# adder_subtractor.net
KiCad netlist of a schematic drawn in EAGLE
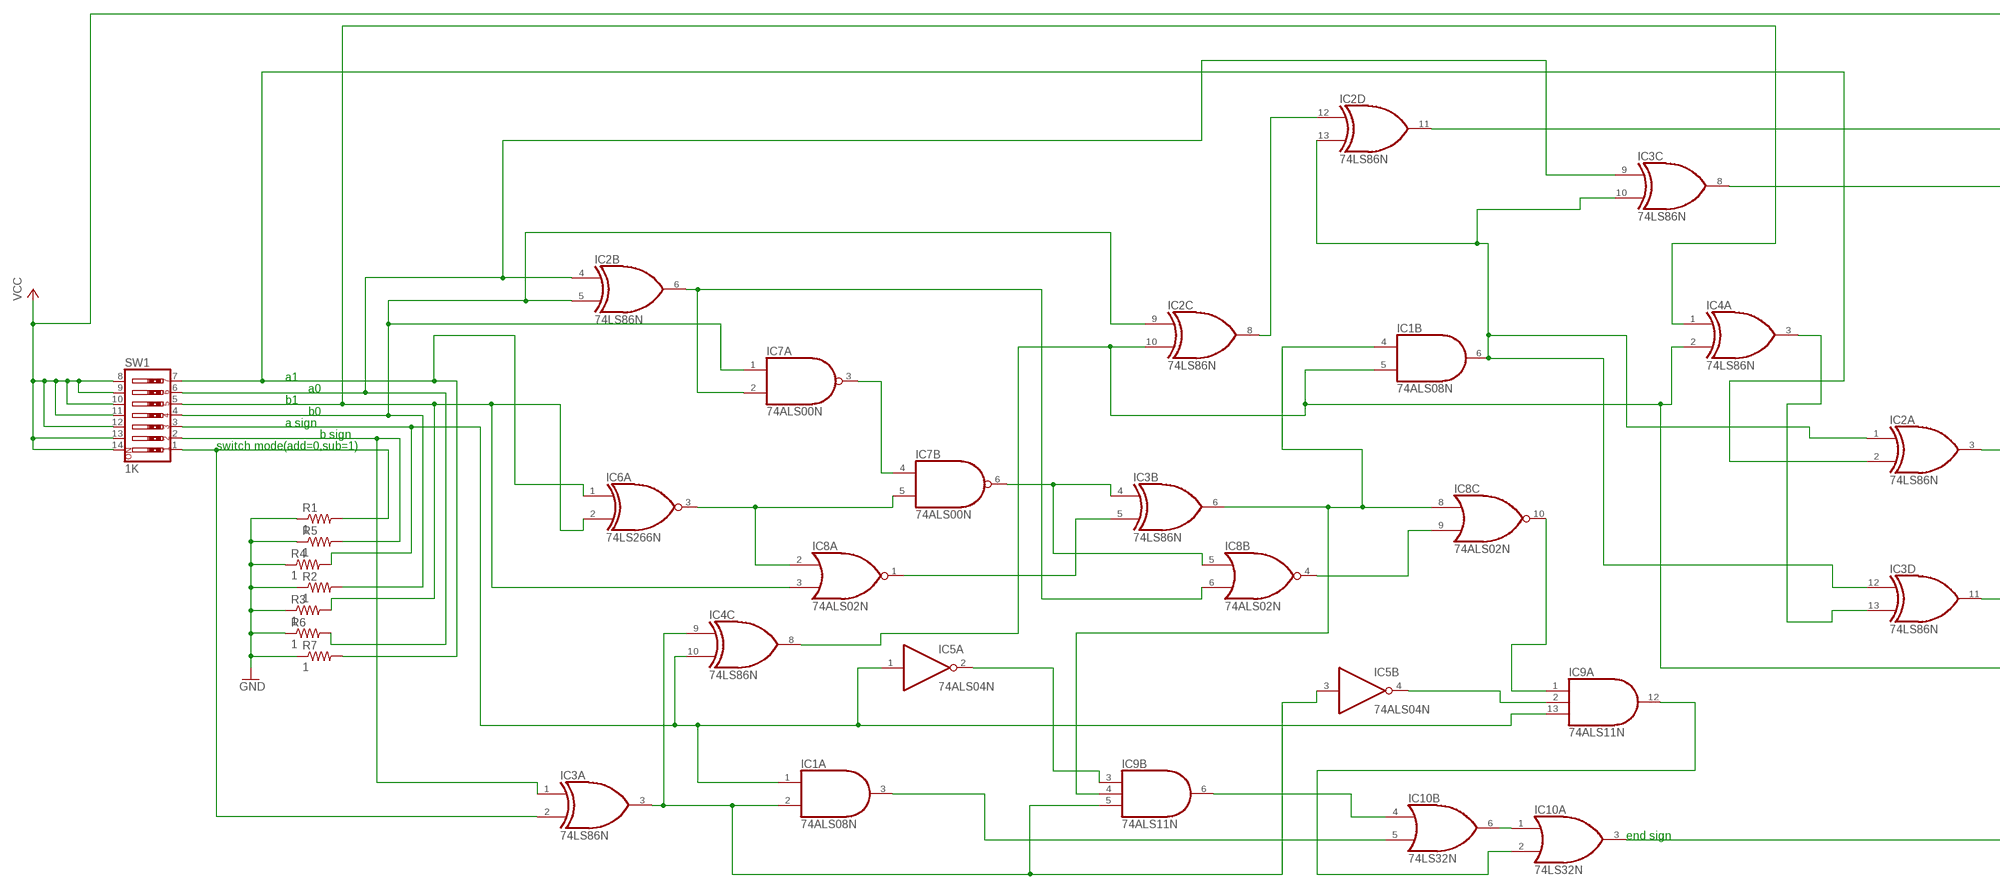
[diagram p0: schematic, sheet 1, part 1 of 2]
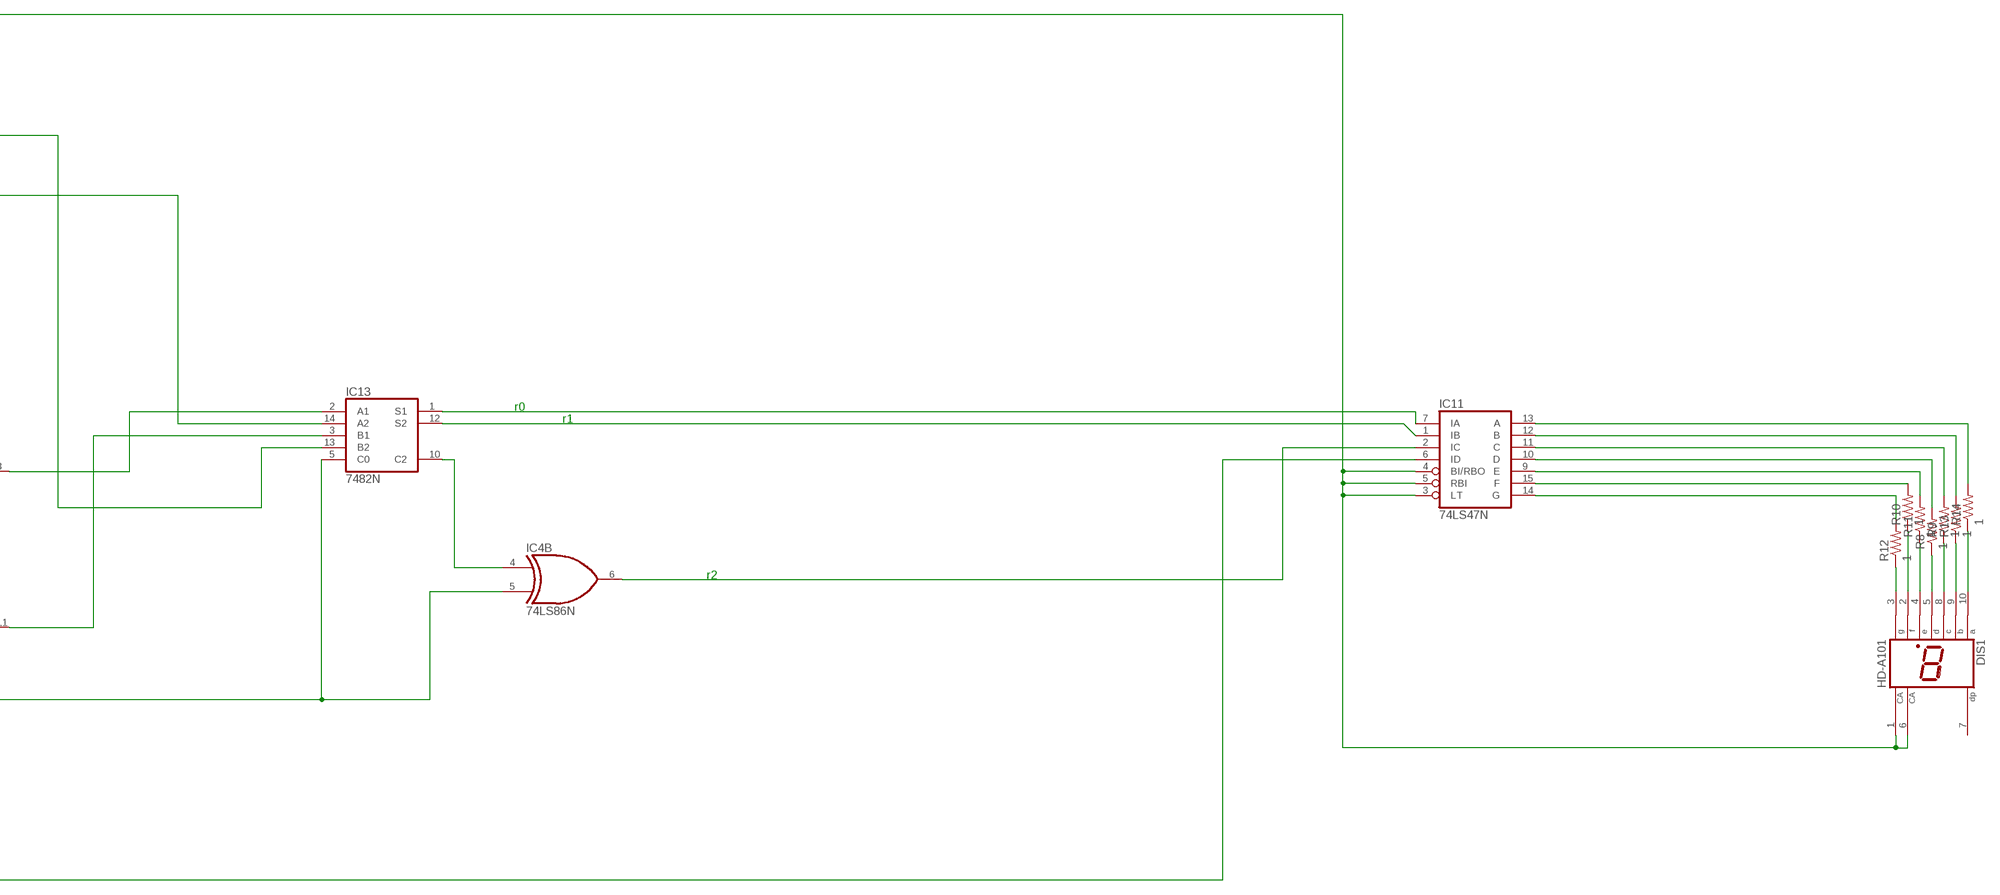
[diagram p1: schematic, sheet 1, part 2 of 2]

(export (version "E")
  (design (tool "Eeschema 10.0.6"))
  (components
    (comp (ref "DIS1")
      (value "HD-A101")
      (footprint "eagle-import:HDSP-A")
      (libsource (lib "eagle-import") (part "HD-A101"))
    )
    (comp (ref "IC1")
      (value "74ALS08N")
      (footprint "eagle-import:DIL14")
      (libsource (lib "eagle-import") (part "7408NALS"))
    )
    (comp (ref "IC2")
      (value "74LS86N")
      (footprint "eagle-import:DIL14")
      (libsource (lib "eagle-import") (part "7486NLS"))
    )
    (comp (ref "IC3")
      (value "74LS86N")
      (footprint "eagle-import:DIL14")
      (libsource (lib "eagle-import") (part "7486NLS"))
    )
    (comp (ref "IC4")
      (value "74LS86N")
      (footprint "eagle-import:DIL14")
      (libsource (lib "eagle-import") (part "7486NLS"))
    )
    (comp (ref "IC5")
      (value "74ALS04N")
      (footprint "eagle-import:DIL14")
      (libsource (lib "eagle-import") (part "7404NALS"))
    )
    (comp (ref "IC6")
      (value "74LS266N")
      (footprint "eagle-import:DIL14")
      (libsource (lib "eagle-import") (part "74266NLS"))
    )
    (comp (ref "IC7")
      (value "74ALS00N")
      (footprint "eagle-import:DIL14")
      (libsource (lib "eagle-import") (part "7400NALS"))
    )
    (comp (ref "IC8")
      (value "74ALS02N")
      (footprint "eagle-import:DIL14")
      (libsource (lib "eagle-import") (part "7402NALS"))
    )
    (comp (ref "IC9")
      (value "74ALS11N")
      (footprint "eagle-import:DIL14")
      (libsource (lib "eagle-import") (part "7411NALS"))
    )
    (comp (ref "IC10")
      (value "74LS32N")
      (footprint "eagle-import:DIL14")
      (libsource (lib "eagle-import") (part "7432NLS"))
    )
    (comp (ref "IC11")
      (value "74LS47N")
      (footprint "eagle-import:DIL16")
      (libsource (lib "eagle-import") (part "7447NLS"))
    )
    (comp (ref "IC13")
      (value "7482N")
      (footprint "eagle-import:DIL14")
      (libsource (lib "eagle-import") (part "7482N"))
    )
    (comp (ref "R1")
      (value "1")
      (footprint "eagle-import:0204V")
      (libsource (lib "eagle-import") (part "R-US_0204/2V"))
    )
    (comp (ref "R2")
      (value "1")
      (footprint "eagle-import:0204V")
      (libsource (lib "eagle-import") (part "R-US_0204/2V"))
    )
    (comp (ref "R3")
      (value "1")
      (footprint "eagle-import:0204V")
      (libsource (lib "eagle-import") (part "R-US_0204/2V"))
    )
    (comp (ref "R4")
      (value "1")
      (footprint "eagle-import:0204V")
      (libsource (lib "eagle-import") (part "R-US_0204/2V"))
    )
    (comp (ref "R5")
      (value "1")
      (footprint "eagle-import:0204V")
      (libsource (lib "eagle-import") (part "R-US_0204/2V"))
    )
    (comp (ref "R6")
      (value "1")
      (footprint "eagle-import:0204V")
      (libsource (lib "eagle-import") (part "R-US_0204/2V"))
    )
    (comp (ref "R7")
      (value "1")
      (footprint "eagle-import:0204V")
      (libsource (lib "eagle-import") (part "R-US_0204/2V"))
    )
    (comp (ref "R8")
      (value "1")
      (footprint "eagle-import:0204V")
      (libsource (lib "eagle-import") (part "R-US_0204/2V"))
    )
    (comp (ref "R9")
      (value "1")
      (footprint "eagle-import:0204V")
      (libsource (lib "eagle-import") (part "R-US_0204/2V"))
    )
    (comp (ref "R10")
      (value "1")
      (footprint "eagle-import:0204V")
      (libsource (lib "eagle-import") (part "R-US_0204/2V"))
    )
    (comp (ref "R11")
      (value "1")
      (footprint "eagle-import:0204V")
      (libsource (lib "eagle-import") (part "R-US_0204/2V"))
    )
    (comp (ref "R12")
      (value "1")
      (footprint "eagle-import:0204V")
      (libsource (lib "eagle-import") (part "R-US_0204/2V"))
    )
    (comp (ref "R13")
      (value "1")
      (footprint "eagle-import:0204V")
      (libsource (lib "eagle-import") (part "R-US_0204/2V"))
    )
    (comp (ref "R14")
      (value "1")
      (footprint "eagle-import:0204V")
      (libsource (lib "eagle-import") (part "R-US_0204/2V"))
    )
    (comp (ref "SW1")
      (value "1K")
      (footprint "eagle-import:EDG-07")
      (libsource (lib "eagle-import") (part "SW_DIP-7"))
    )
  )
  (nets
    (net (code "1") (name "GND") (class "Default")
      (node (ref "R1") (pin "1") (pinfunction "1_1") (pintype "passive"))
      (node (ref "R2") (pin "1") (pinfunction "1_1") (pintype "passive"))
      (node (ref "R3") (pin "1") (pinfunction "1_1") (pintype "passive"))
      (node (ref "R4") (pin "1") (pinfunction "1_1") (pintype "passive"))
      (node (ref "R5") (pin "1") (pinfunction "1_1") (pintype "passive"))
      (node (ref "R6") (pin "1") (pinfunction "1_1") (pintype "passive"))
      (node (ref "R7") (pin "1") (pinfunction "1_1") (pintype "passive"))
    )
    (net (code "2") (name "Net-(DIS1-A)") (class "Default")
      (node (ref "DIS1") (pin "10") (pinfunction "A_10") (pintype "passive"))
      (node (ref "R14") (pin "1") (pinfunction "1_1") (pintype "passive"))
    )
    (net (code "3") (name "Net-(DIS1-B)") (class "Default")
      (node (ref "DIS1") (pin "9") (pinfunction "B_9") (pintype "passive"))
      (node (ref "R13") (pin "1") (pinfunction "1_1") (pintype "passive"))
    )
    (net (code "4") (name "Net-(DIS1-C)") (class "Default")
      (node (ref "DIS1") (pin "8") (pinfunction "C_8") (pintype "passive"))
      (node (ref "R9") (pin "1") (pinfunction "1_1") (pintype "passive"))
    )
    (net (code "5") (name "Net-(DIS1-D)") (class "Default")
      (node (ref "DIS1") (pin "5") (pinfunction "D_5") (pintype "passive"))
      (node (ref "R8") (pin "1") (pinfunction "1_1") (pintype "passive"))
    )
    (net (code "6") (name "Net-(DIS1-E)") (class "Default")
      (node (ref "DIS1") (pin "4") (pinfunction "E_4") (pintype "passive"))
      (node (ref "R11") (pin "1") (pinfunction "1_1") (pintype "passive"))
    )
    (net (code "7") (name "Net-(DIS1-F)") (class "Default")
      (node (ref "DIS1") (pin "2") (pinfunction "F_2") (pintype "passive"))
      (node (ref "R10") (pin "1") (pinfunction "1_1") (pintype "passive"))
    )
    (net (code "8") (name "Net-(DIS1-G)") (class "Default")
      (node (ref "DIS1") (pin "3") (pinfunction "G_3") (pintype "passive"))
      (node (ref "R12") (pin "1") (pinfunction "1_1") (pintype "passive"))
    )
    (net (code "9") (name "Net-(IC1A-I0)") (class "Default")
      (node (ref "IC1") (pin "1") (pinfunction "I0_1") (pintype "input"))
      (node (ref "IC4") (pin "10") (pinfunction "I1_10") (pintype "input"))
      (node (ref "IC5") (pin "1") (pinfunction "I_1") (pintype "input"))
      (node (ref "IC9") (pin "13") (pinfunction "I2_13") (pintype "input"))
      (node (ref "R4") (pin "2") (pinfunction "2_2") (pintype "passive"))
      (node (ref "SW1") (pin "3") (pinfunction "3_3") (pintype "passive"))
    )
    (net (code "10") (name "Net-(IC1A-I1)") (class "Default")
      (node (ref "IC1") (pin "2") (pinfunction "I1_2") (pintype "input"))
      (node (ref "IC3") (pin "3") (pinfunction "O_3") (pintype "output"))
      (node (ref "IC4") (pin "9") (pinfunction "I0_9") (pintype "input"))
      (node (ref "IC5") (pin "3") (pinfunction "I_3") (pintype "input"))
      (node (ref "IC9") (pin "5") (pinfunction "I2_5") (pintype "input"))
    )
    (net (code "11") (name "Net-(IC1B-I0)") (class "Default")
      (node (ref "IC1") (pin "4") (pinfunction "I0_4") (pintype "input"))
      (node (ref "IC3") (pin "6") (pinfunction "O_6") (pintype "output"))
      (node (ref "IC8") (pin "8") (pinfunction "I0_8") (pintype "input"))
      (node (ref "IC9") (pin "4") (pinfunction "I1_4") (pintype "input"))
    )
    (net (code "12") (name "Net-(IC1B-O)") (class "Default")
      (node (ref "IC1") (pin "6") (pinfunction "O_6") (pintype "output"))
      (node (ref "IC2") (pin "1") (pinfunction "I0_1") (pintype "input"))
      (node (ref "IC2") (pin "13") (pinfunction "I1_13") (pintype "input"))
      (node (ref "IC3") (pin "10") (pinfunction "I1_10") (pintype "input"))
      (node (ref "IC3") (pin "12") (pinfunction "I0_12") (pintype "input"))
    )
    (net (code "13") (name "Net-(IC2A-I1)") (class "Default")
      (node (ref "IC2") (pin "2") (pinfunction "I1_2") (pintype "input"))
      (node (ref "IC6") (pin "1") (pinfunction "I0_1") (pintype "input"))
      (node (ref "R7") (pin "2") (pinfunction "2_2") (pintype "passive"))
      (node (ref "SW1") (pin "7") (pinfunction "7_7") (pintype "passive"))
    )
    (net (code "14") (name "Net-(IC2B-I0)") (class "Default")
      (node (ref "IC2") (pin "4") (pinfunction "I0_4") (pintype "input"))
      (node (ref "IC3") (pin "9") (pinfunction "I0_9") (pintype "input"))
      (node (ref "R6") (pin "2") (pinfunction "2_2") (pintype "passive"))
      (node (ref "SW1") (pin "6") (pinfunction "6_6") (pintype "passive"))
    )
    (net (code "15") (name "Net-(IC2B-I1)") (class "Default")
      (node (ref "IC2") (pin "5") (pinfunction "I1_5") (pintype "input"))
      (node (ref "IC2") (pin "9") (pinfunction "I0_9") (pintype "input"))
      (node (ref "IC7") (pin "1") (pinfunction "I0_1") (pintype "input"))
      (node (ref "R2") (pin "2") (pinfunction "2_2") (pintype "passive"))
      (node (ref "SW1") (pin "4") (pinfunction "4_4") (pintype "passive"))
    )
    (net (code "16") (name "Net-(IC2B-O)") (class "Default")
      (node (ref "IC2") (pin "6") (pinfunction "O_6") (pintype "output"))
      (node (ref "IC7") (pin "2") (pinfunction "I1_2") (pintype "input"))
      (node (ref "IC8") (pin "6") (pinfunction "I1_6") (pintype "input"))
    )
    (net (code "17") (name "Net-(IC2C-O)") (class "Default")
      (node (ref "IC2") (pin "12") (pinfunction "I0_12") (pintype "input"))
      (node (ref "IC2") (pin "8") (pinfunction "O_8") (pintype "output"))
    )
    (net (code "18") (name "Net-(IC3A-I0)") (class "Default")
      (node (ref "IC3") (pin "1") (pinfunction "I0_1") (pintype "input"))
      (node (ref "R5") (pin "2") (pinfunction "2_2") (pintype "passive"))
      (node (ref "SW1") (pin "2") (pinfunction "2_2") (pintype "passive"))
    )
    (net (code "19") (name "Net-(IC3A-I1)") (class "Default")
      (node (ref "IC3") (pin "2") (pinfunction "I1_2") (pintype "input"))
      (node (ref "R1") (pin "2") (pinfunction "2_2") (pintype "passive"))
      (node (ref "SW1") (pin "1") (pinfunction "1_1") (pintype "passive"))
    )
    (net (code "20") (name "Net-(IC3B-I0)") (class "Default")
      (node (ref "IC3") (pin "4") (pinfunction "I0_4") (pintype "input"))
      (node (ref "IC7") (pin "6") (pinfunction "O_6") (pintype "output"))
      (node (ref "IC8") (pin "5") (pinfunction "I0_5") (pintype "input"))
    )
    (net (code "21") (name "Net-(IC3B-I1)") (class "Default")
      (node (ref "IC3") (pin "5") (pinfunction "I1_5") (pintype "input"))
      (node (ref "IC8") (pin "1") (pinfunction "O_1") (pintype "output"))
    )
    (net (code "22") (name "Net-(IC3D-I1)") (class "Default")
      (node (ref "IC3") (pin "13") (pinfunction "I1_13") (pintype "input"))
      (node (ref "IC4") (pin "3") (pinfunction "O_3") (pintype "output"))
    )
    (net (code "23") (name "Net-(IC4A-I0)") (class "Default")
      (node (ref "IC4") (pin "1") (pinfunction "I0_1") (pintype "input"))
      (node (ref "IC6") (pin "2") (pinfunction "I1_2") (pintype "input"))
      (node (ref "IC8") (pin "3") (pinfunction "I1_3") (pintype "input"))
      (node (ref "R3") (pin "2") (pinfunction "2_2") (pintype "passive"))
      (node (ref "SW1") (pin "5") (pinfunction "5_5") (pintype "passive"))
    )
    (net (code "24") (name "Net-(IC5A-O)") (class "Default")
      (node (ref "IC5") (pin "2") (pinfunction "O_2") (pintype "output"))
      (node (ref "IC9") (pin "3") (pinfunction "I0_3") (pintype "input"))
    )
    (net (code "25") (name "Net-(IC5B-O)") (class "Default")
      (node (ref "IC5") (pin "4") (pinfunction "O_4") (pintype "output"))
      (node (ref "IC9") (pin "2") (pinfunction "I1_2") (pintype "input"))
    )
    (net (code "26") (name "Net-(IC6A-O)") (class "Default")
      (node (ref "IC6") (pin "3") (pinfunction "O_3") (pintype "open_collector"))
      (node (ref "IC7") (pin "5") (pinfunction "I1_5") (pintype "input"))
      (node (ref "IC8") (pin "2") (pinfunction "I0_2") (pintype "input"))
    )
    (net (code "27") (name "Net-(IC7A-O)") (class "Default")
      (node (ref "IC7") (pin "3") (pinfunction "O_3") (pintype "output"))
      (node (ref "IC7") (pin "4") (pinfunction "I0_4") (pintype "input"))
    )
    (net (code "28") (name "Net-(IC8B-O)") (class "Default")
      (node (ref "IC8") (pin "4") (pinfunction "O_4") (pintype "output"))
      (node (ref "IC8") (pin "9") (pinfunction "I1_9") (pintype "input"))
    )
    (net (code "29") (name "Net-(IC8C-O)") (class "Default")
      (node (ref "IC8") (pin "10") (pinfunction "O_10") (pintype "output"))
      (node (ref "IC9") (pin "1") (pinfunction "I0_1") (pintype "input"))
    )
    (net (code "30") (name "Net-(IC10A-I0)") (class "Default")
      (node (ref "IC10") (pin "1") (pinfunction "I0_1") (pintype "input"))
      (node (ref "IC10") (pin "6") (pinfunction "O_6") (pintype "output"))
    )
    (net (code "31") (name "Net-(IC10A-I1)") (class "Default")
      (node (ref "IC10") (pin "2") (pinfunction "I1_2") (pintype "input"))
      (node (ref "IC9") (pin "12") (pinfunction "O_12") (pintype "output"))
    )
    (net (code "32") (name "Net-(IC10A-O)") (class "Default")
      (node (ref "IC10") (pin "3") (pinfunction "O_3") (pintype "output"))
      (node (ref "IC11") (pin "6") (pinfunction "ID_6") (pintype "input"))
    )
    (net (code "33") (name "Net-(IC10B-I0)") (class "Default")
      (node (ref "IC10") (pin "4") (pinfunction "I0_4") (pintype "input"))
      (node (ref "IC9") (pin "6") (pinfunction "O_6") (pintype "output"))
    )
    (net (code "34") (name "Net-(IC10B-I1)") (class "Default")
      (node (ref "IC1") (pin "3") (pinfunction "O_3") (pintype "output"))
      (node (ref "IC10") (pin "5") (pinfunction "I1_5") (pintype "input"))
    )
    (net (code "35") (name "Net-(IC11A-A)") (class "Default")
      (node (ref "IC11") (pin "13") (pinfunction "A_13") (pintype "output"))
      (node (ref "R14") (pin "2") (pinfunction "2_2") (pintype "passive"))
    )
    (net (code "36") (name "Net-(IC11A-B)") (class "Default")
      (node (ref "IC11") (pin "12") (pinfunction "B_12") (pintype "output"))
      (node (ref "R13") (pin "2") (pinfunction "2_2") (pintype "passive"))
    )
    (net (code "37") (name "Net-(IC11A-C)") (class "Default")
      (node (ref "IC11") (pin "11") (pinfunction "C_11") (pintype "output"))
      (node (ref "R9") (pin "2") (pinfunction "2_2") (pintype "passive"))
    )
    (net (code "38") (name "Net-(IC11A-D)") (class "Default")
      (node (ref "IC11") (pin "10") (pinfunction "D_10") (pintype "output"))
      (node (ref "R8") (pin "2") (pinfunction "2_2") (pintype "passive"))
    )
    (net (code "39") (name "Net-(IC11A-E)") (class "Default")
      (node (ref "IC11") (pin "9") (pinfunction "E_9") (pintype "output"))
      (node (ref "R11") (pin "2") (pinfunction "2_2") (pintype "passive"))
    )
    (net (code "40") (name "Net-(IC11A-F)") (class "Default")
      (node (ref "IC11") (pin "15") (pinfunction "F_15") (pintype "output"))
      (node (ref "R10") (pin "2") (pinfunction "2_2") (pintype "passive"))
    )
    (net (code "41") (name "Net-(IC11A-G)") (class "Default")
      (node (ref "IC11") (pin "14") (pinfunction "G_14") (pintype "output"))
      (node (ref "R12") (pin "2") (pinfunction "2_2") (pintype "passive"))
    )
    (net (code "42") (name "Net-(IC11A-IA)") (class "Default")
      (node (ref "IC11") (pin "7") (pinfunction "IA_7") (pintype "input"))
      (node (ref "IC13") (pin "1") (pinfunction "S1_1") (pintype "output"))
    )
    (net (code "43") (name "Net-(IC11A-IB)") (class "Default")
      (node (ref "IC11") (pin "1") (pinfunction "IB_1") (pintype "input"))
      (node (ref "IC13") (pin "12") (pinfunction "S2_12") (pintype "output"))
    )
    (net (code "44") (name "Net-(IC11A-IC)") (class "Default")
      (node (ref "IC11") (pin "2") (pinfunction "IC_2") (pintype "input"))
      (node (ref "IC4") (pin "6") (pinfunction "O_6") (pintype "output"))
    )
    (net (code "45") (name "Net-(IC13A-A1)") (class "Default")
      (node (ref "IC13") (pin "2") (pinfunction "A1_2") (pintype "input"))
      (node (ref "IC2") (pin "3") (pinfunction "O_3") (pintype "output"))
    )
    (net (code "46") (name "Net-(IC13A-A2)") (class "Default")
      (node (ref "IC13") (pin "14") (pinfunction "A2_14") (pintype "input"))
      (node (ref "IC3") (pin "8") (pinfunction "O_8") (pintype "output"))
    )
    (net (code "47") (name "Net-(IC13A-B1)") (class "Default")
      (node (ref "IC13") (pin "3") (pinfunction "B1_3") (pintype "input"))
      (node (ref "IC3") (pin "11") (pinfunction "O_11") (pintype "output"))
    )
    (net (code "48") (name "Net-(IC13A-B2)") (class "Default")
      (node (ref "IC13") (pin "13") (pinfunction "B2_13") (pintype "input"))
      (node (ref "IC2") (pin "11") (pinfunction "O_11") (pintype "output"))
    )
    (net (code "49") (name "Net-(IC13A-C0)") (class "Default")
      (node (ref "IC1") (pin "5") (pinfunction "I1_5") (pintype "input"))
      (node (ref "IC13") (pin "5") (pinfunction "C0_5") (pintype "input"))
      (node (ref "IC2") (pin "10") (pinfunction "I1_10") (pintype "input"))
      (node (ref "IC4") (pin "2") (pinfunction "I1_2") (pintype "input"))
      (node (ref "IC4") (pin "5") (pinfunction "I1_5") (pintype "input"))
      (node (ref "IC4") (pin "8") (pinfunction "O_8") (pintype "output"))
    )
    (net (code "50") (name "Net-(IC13A-C2)") (class "Default")
      (node (ref "IC13") (pin "10") (pinfunction "C2_10") (pintype "output"))
      (node (ref "IC4") (pin "4") (pinfunction "I0_4") (pintype "input"))
    )
    (net (code "51") (name "VCC") (class "Default")
      (node (ref "DIS1") (pin "1") (pinfunction "CA_1") (pintype "passive"))
      (node (ref "DIS1") (pin "6") (pinfunction "CA_6") (pintype "passive"))
      (node (ref "IC11") (pin "3") (pinfunction "LT_3") (pintype "input"))
      (node (ref "IC11") (pin "4") (pinfunction "BI/RBO_4") (pintype "input"))
      (node (ref "IC11") (pin "5") (pinfunction "RBI_5") (pintype "input"))
      (node (ref "SW1") (pin "10") (pinfunction "10_10") (pintype "passive"))
      (node (ref "SW1") (pin "11") (pinfunction "11_11") (pintype "passive"))
      (node (ref "SW1") (pin "12") (pinfunction "12_12") (pintype "passive"))
      (node (ref "SW1") (pin "13") (pinfunction "13_13") (pintype "passive"))
      (node (ref "SW1") (pin "14") (pinfunction "14_14") (pintype "passive"))
      (node (ref "SW1") (pin "8") (pinfunction "8_8") (pintype "passive"))
      (node (ref "SW1") (pin "9") (pinfunction "9_9") (pintype "passive"))
    )
    (net (code "52") (name "unconnected-(DIS1-DP-Pad7)") (class "Default")
      (node (ref "DIS1") (pin "7") (pinfunction "DP_7") (pintype "passive"))
    )
  )
)
